# SnowFlake.net
KiCad netlist of a schematic drawn in EAGLE
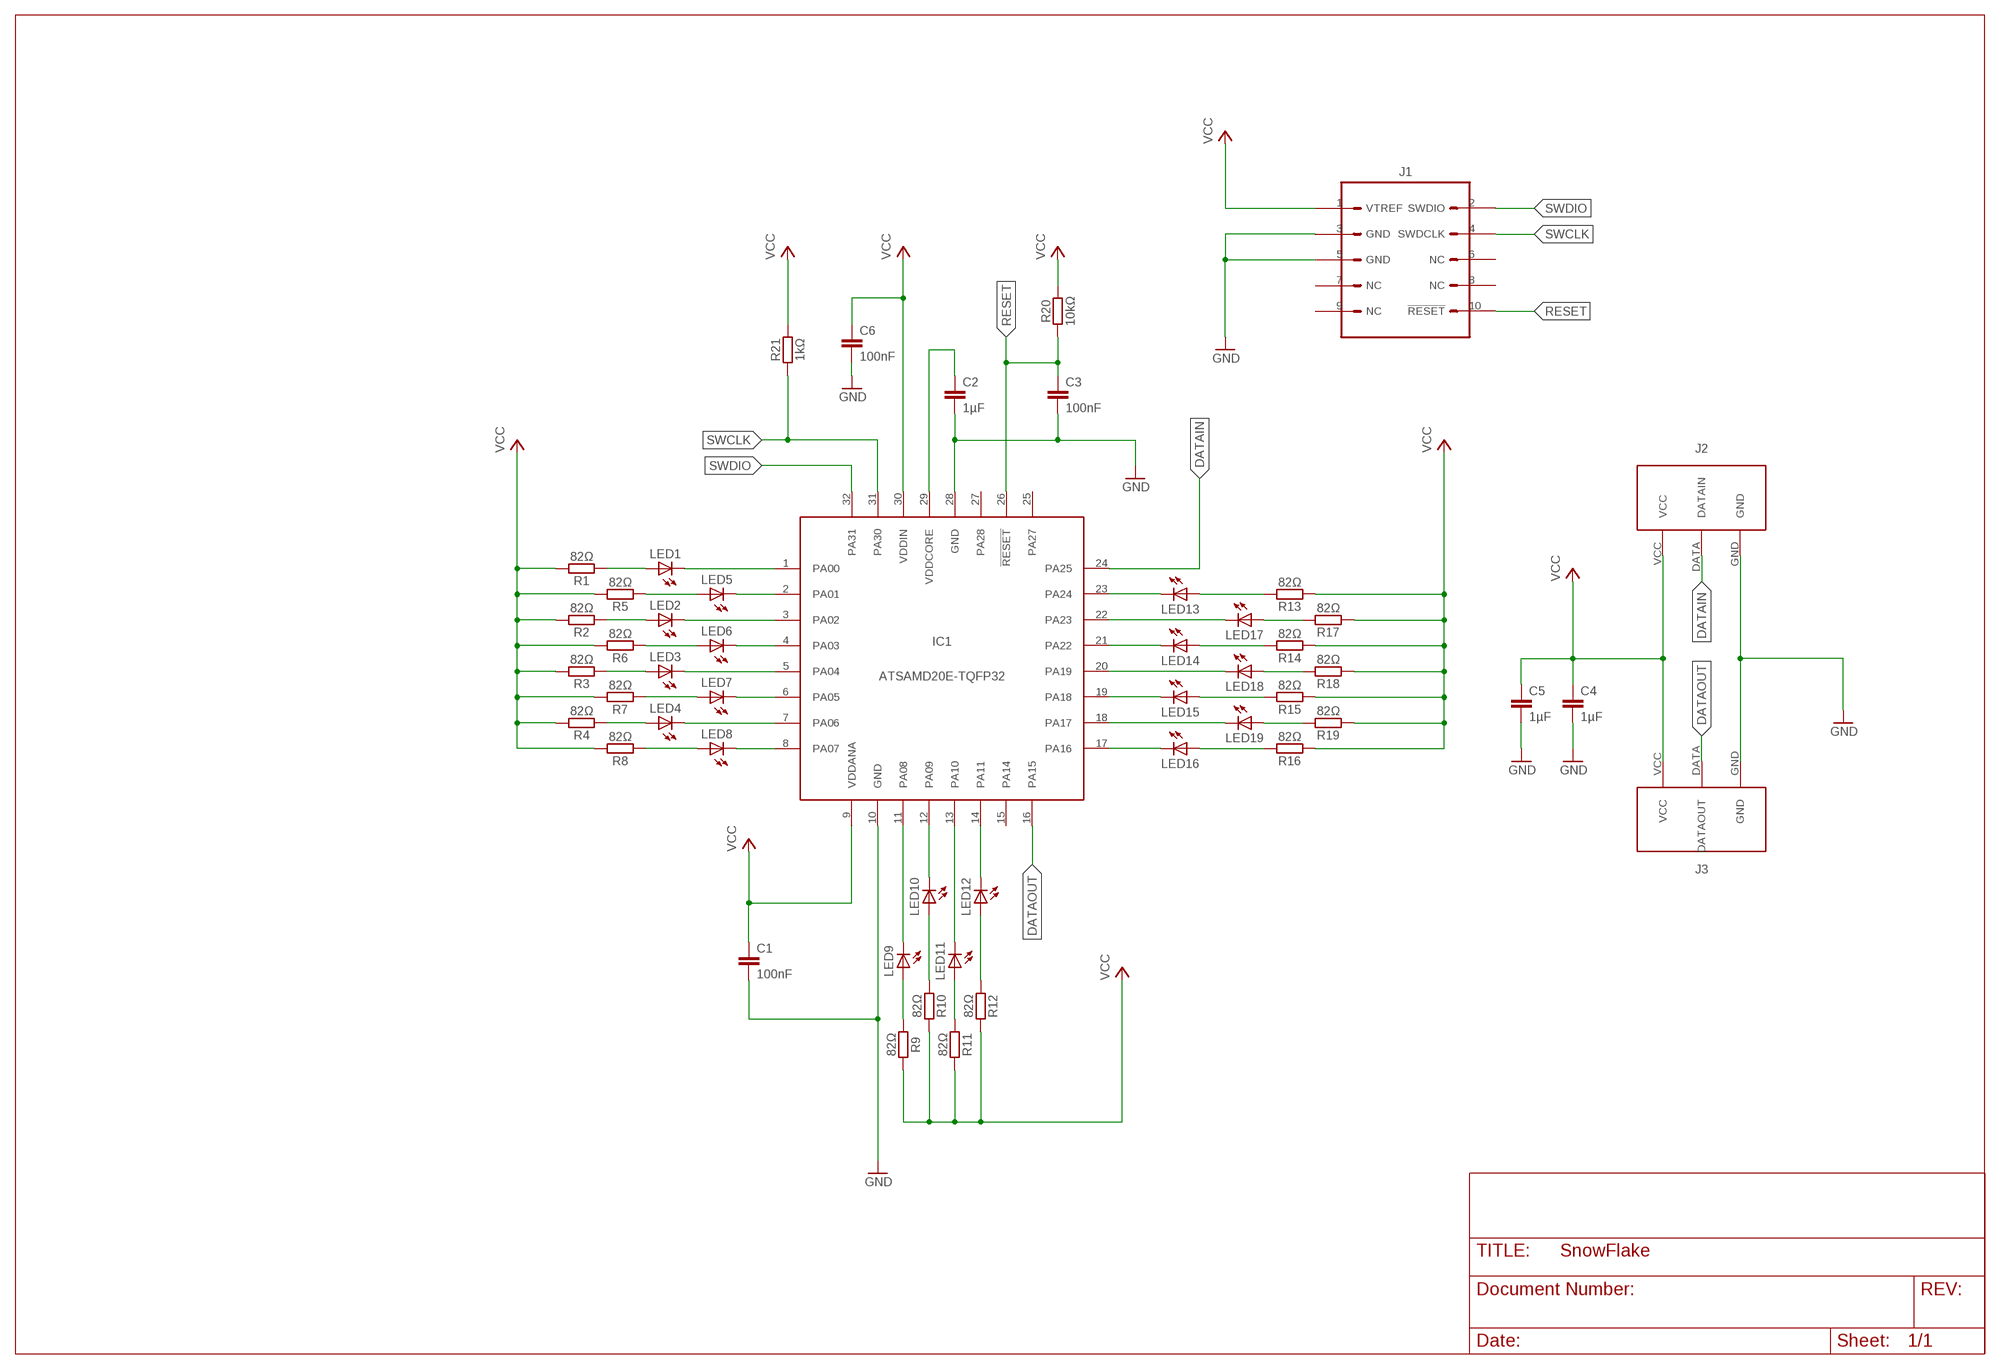
[diagram p0: schematic, sheet 1]

(export (version "E")
  (design (tool "Eeschema 10.0.6"))
  (components
    (comp (ref "C1")
      (value "100nF")
      (footprint "eagle-import:CAPACITOR-0805-MURATA-GRM-21")
      (libsource (lib "eagle-import") (part "C0805-MURATA-GRM-21"))
    )
    (comp (ref "C2")
      (value "1µF")
      (footprint "eagle-import:CAPACITOR-0805-MURATA-GRM-21")
      (libsource (lib "eagle-import") (part "C0805-MURATA-GRM-21"))
    )
    (comp (ref "C3")
      (value "100nF")
      (footprint "eagle-import:CAPACITOR-0805-MURATA-GRM-21")
      (libsource (lib "eagle-import") (part "C0805-MURATA-GRM-21"))
    )
    (comp (ref "C4")
      (value "1µF")
      (footprint "eagle-import:CAPACITOR-0805-MURATA-GRM-21")
      (libsource (lib "eagle-import") (part "C0805-MURATA-GRM-21"))
    )
    (comp (ref "C5")
      (value "1µF")
      (footprint "eagle-import:CAPACITOR-0805-MURATA-GRM-21")
      (libsource (lib "eagle-import") (part "C0805-MURATA-GRM-21"))
    )
    (comp (ref "C6")
      (value "100nF")
      (footprint "eagle-import:CAPACITOR-0805-MURATA-GRM-21")
      (libsource (lib "eagle-import") (part "C0805-MURATA-GRM-21"))
    )
    (comp (ref "IC1")
      (value "ATSAMD20E-TQFP32")
      (footprint "eagle-import:TQFP32-08")
      (libsource (lib "eagle-import") (part "ATSAMD20E-TQFP32"))
    )
    (comp (ref "J1")
      (value "CON-CORTEX-DEBUG-SMD1.27")
      (footprint "eagle-import:CON-2X5-HARWIN-1.27")
      (libsource (lib "eagle-import") (part "CON-CORTEX-DEBUG-SMD1.27"))
    )
    (comp (ref "J2")
      (value "CON-SNOWF-IN")
      (footprint "eagle-import:CON-PADS-3XWIRE-B")
      (libsource (lib "eagle-import") (part "CON-SNOWF-IN"))
    )
    (comp (ref "J3")
      (value "CON-SNOWF-OUT")
      (footprint "eagle-import:CON-PADS-3XWIRE-T")
      (libsource (lib "eagle-import") (part "CON-SNOWF-OUT"))
    )
    (comp (ref "LED1")
      (value "LED0402")
      (footprint "eagle-import:LED-0402-ROHM")
      (libsource (lib "eagle-import") (part "LED0402"))
    )
    (comp (ref "LED2")
      (value "LED0402")
      (footprint "eagle-import:LED-0402-ROHM")
      (libsource (lib "eagle-import") (part "LED0402"))
    )
    (comp (ref "LED3")
      (value "LED0402")
      (footprint "eagle-import:LED-0402-ROHM")
      (libsource (lib "eagle-import") (part "LED0402"))
    )
    (comp (ref "LED4")
      (value "LED0402")
      (footprint "eagle-import:LED-0402-ROHM")
      (libsource (lib "eagle-import") (part "LED0402"))
    )
    (comp (ref "LED5")
      (value "LED0402")
      (footprint "eagle-import:LED-0402-ROHM")
      (libsource (lib "eagle-import") (part "LED0402"))
    )
    (comp (ref "LED6")
      (value "LED0402")
      (footprint "eagle-import:LED-0402-ROHM")
      (libsource (lib "eagle-import") (part "LED0402"))
    )
    (comp (ref "LED7")
      (value "LED0402")
      (footprint "eagle-import:LED-0402-ROHM")
      (libsource (lib "eagle-import") (part "LED0402"))
    )
    (comp (ref "LED8")
      (value "LED0402")
      (footprint "eagle-import:LED-0402-ROHM")
      (libsource (lib "eagle-import") (part "LED0402"))
    )
    (comp (ref "LED9")
      (value "LED0402")
      (footprint "eagle-import:LED-0402-ROHM")
      (libsource (lib "eagle-import") (part "LED0402"))
    )
    (comp (ref "LED10")
      (value "LED0402")
      (footprint "eagle-import:LED-0402-ROHM")
      (libsource (lib "eagle-import") (part "LED0402"))
    )
    (comp (ref "LED11")
      (value "LED0402")
      (footprint "eagle-import:LED-0402-ROHM")
      (libsource (lib "eagle-import") (part "LED0402"))
    )
    (comp (ref "LED12")
      (value "LED0402")
      (footprint "eagle-import:LED-0402-ROHM")
      (libsource (lib "eagle-import") (part "LED0402"))
    )
    (comp (ref "LED13")
      (value "LED0402")
      (footprint "eagle-import:LED-0402-ROHM")
      (libsource (lib "eagle-import") (part "LED0402"))
    )
    (comp (ref "LED14")
      (value "LED0402")
      (footprint "eagle-import:LED-0402-ROHM")
      (libsource (lib "eagle-import") (part "LED0402"))
    )
    (comp (ref "LED15")
      (value "LED0402")
      (footprint "eagle-import:LED-0402-ROHM")
      (libsource (lib "eagle-import") (part "LED0402"))
    )
    (comp (ref "LED16")
      (value "LED0402")
      (footprint "eagle-import:LED-0402-ROHM")
      (libsource (lib "eagle-import") (part "LED0402"))
    )
    (comp (ref "LED17")
      (value "LED0402")
      (footprint "eagle-import:LED-0402-ROHM")
      (libsource (lib "eagle-import") (part "LED0402"))
    )
    (comp (ref "LED18")
      (value "LED0402")
      (footprint "eagle-import:LED-0402-ROHM")
      (libsource (lib "eagle-import") (part "LED0402"))
    )
    (comp (ref "LED19")
      (value "LED0402")
      (footprint "eagle-import:LED-0402-ROHM")
      (libsource (lib "eagle-import") (part "LED0402"))
    )
    (comp (ref "R1")
      (value "82Ω")
      (footprint "eagle-import:RESISTOR-0805-KOA-RK73-2A")
      (libsource (lib "eagle-import") (part "RESISTOR0805-KOA-RK73-2A"))
    )
    (comp (ref "R2")
      (value "82Ω")
      (footprint "eagle-import:RESISTOR-0805-KOA-RK73-2A")
      (libsource (lib "eagle-import") (part "RESISTOR0805-KOA-RK73-2A"))
    )
    (comp (ref "R3")
      (value "82Ω")
      (footprint "eagle-import:RESISTOR-0805-KOA-RK73-2A")
      (libsource (lib "eagle-import") (part "RESISTOR0805-KOA-RK73-2A"))
    )
    (comp (ref "R4")
      (value "82Ω")
      (footprint "eagle-import:RESISTOR-0805-KOA-RK73-2A")
      (libsource (lib "eagle-import") (part "RESISTOR0805-KOA-RK73-2A"))
    )
    (comp (ref "R5")
      (value "82Ω")
      (footprint "eagle-import:RESISTOR-0805-KOA-RK73-2A")
      (libsource (lib "eagle-import") (part "RESISTOR0805-KOA-RK73-2A"))
    )
    (comp (ref "R6")
      (value "82Ω")
      (footprint "eagle-import:RESISTOR-0805-KOA-RK73-2A")
      (libsource (lib "eagle-import") (part "RESISTOR0805-KOA-RK73-2A"))
    )
    (comp (ref "R7")
      (value "82Ω")
      (footprint "eagle-import:RESISTOR-0805-KOA-RK73-2A")
      (libsource (lib "eagle-import") (part "RESISTOR0805-KOA-RK73-2A"))
    )
    (comp (ref "R8")
      (value "82Ω")
      (footprint "eagle-import:RESISTOR-0805-KOA-RK73-2A")
      (libsource (lib "eagle-import") (part "RESISTOR0805-KOA-RK73-2A"))
    )
    (comp (ref "R9")
      (value "82Ω")
      (footprint "eagle-import:RESISTOR-0805-KOA-RK73-2A")
      (libsource (lib "eagle-import") (part "RESISTOR0805-KOA-RK73-2A"))
    )
    (comp (ref "R10")
      (value "82Ω")
      (footprint "eagle-import:RESISTOR-0805-KOA-RK73-2A")
      (libsource (lib "eagle-import") (part "RESISTOR0805-KOA-RK73-2A"))
    )
    (comp (ref "R11")
      (value "82Ω")
      (footprint "eagle-import:RESISTOR-0805-KOA-RK73-2A")
      (libsource (lib "eagle-import") (part "RESISTOR0805-KOA-RK73-2A"))
    )
    (comp (ref "R12")
      (value "82Ω")
      (footprint "eagle-import:RESISTOR-0805-KOA-RK73-2A")
      (libsource (lib "eagle-import") (part "RESISTOR0805-KOA-RK73-2A"))
    )
    (comp (ref "R13")
      (value "82Ω")
      (footprint "eagle-import:RESISTOR-0805-KOA-RK73-2A")
      (libsource (lib "eagle-import") (part "RESISTOR0805-KOA-RK73-2A"))
    )
    (comp (ref "R14")
      (value "82Ω")
      (footprint "eagle-import:RESISTOR-0805-KOA-RK73-2A")
      (libsource (lib "eagle-import") (part "RESISTOR0805-KOA-RK73-2A"))
    )
    (comp (ref "R15")
      (value "82Ω")
      (footprint "eagle-import:RESISTOR-0805-KOA-RK73-2A")
      (libsource (lib "eagle-import") (part "RESISTOR0805-KOA-RK73-2A"))
    )
    (comp (ref "R16")
      (value "82Ω")
      (footprint "eagle-import:RESISTOR-0805-KOA-RK73-2A")
      (libsource (lib "eagle-import") (part "RESISTOR0805-KOA-RK73-2A"))
    )
    (comp (ref "R17")
      (value "82Ω")
      (footprint "eagle-import:RESISTOR-0805-KOA-RK73-2A")
      (libsource (lib "eagle-import") (part "RESISTOR0805-KOA-RK73-2A"))
    )
    (comp (ref "R18")
      (value "82Ω")
      (footprint "eagle-import:RESISTOR-0805-KOA-RK73-2A")
      (libsource (lib "eagle-import") (part "RESISTOR0805-KOA-RK73-2A"))
    )
    (comp (ref "R19")
      (value "82Ω")
      (footprint "eagle-import:RESISTOR-0805-KOA-RK73-2A")
      (libsource (lib "eagle-import") (part "RESISTOR0805-KOA-RK73-2A"))
    )
    (comp (ref "R20")
      (value "10kΩ")
      (footprint "eagle-import:RESISTOR-0805-KOA-RK73-2A")
      (libsource (lib "eagle-import") (part "RESISTOR0805-KOA-RK73-2A"))
    )
    (comp (ref "R21")
      (value "1kΩ")
      (footprint "eagle-import:RESISTOR-0805-KOA-RK73-2A")
      (libsource (lib "eagle-import") (part "RESISTOR0805-KOA-RK73-2A"))
    )
  )
  (nets
    (net (code "1") (name "DATAIN") (class "Default")
      (node (ref "IC1") (pin "24") (pinfunction "PA25_24") (pintype "bidirectional"))
      (node (ref "J2") (pin "DATA") (pinfunction "DATAIN_DATA") (pintype "input"))
    )
    (net (code "2") (name "DATAOUT") (class "Default")
      (node (ref "IC1") (pin "16") (pinfunction "PA15_16") (pintype "bidirectional"))
      (node (ref "J3") (pin "DATA") (pinfunction "DATAOUT_DATA") (pintype "output"))
    )
    (net (code "3") (name "GND") (class "Default")
      (node (ref "C1") (pin "2") (pinfunction "2_2") (pintype "passive"))
      (node (ref "C2") (pin "2") (pinfunction "2_2") (pintype "passive"))
      (node (ref "C3") (pin "2") (pinfunction "2_2") (pintype "passive"))
      (node (ref "C4") (pin "2") (pinfunction "2_2") (pintype "passive"))
      (node (ref "C5") (pin "2") (pinfunction "2_2") (pintype "passive"))
      (node (ref "C6") (pin "2") (pinfunction "2_2") (pintype "passive"))
      (node (ref "IC1") (pin "10") (pinfunction "GND_10") (pintype "bidirectional"))
      (node (ref "IC1") (pin "28") (pinfunction "GND_28") (pintype "bidirectional"))
      (node (ref "J1") (pin "3") (pinfunction "GND_3") (pintype "bidirectional"))
      (node (ref "J1") (pin "5") (pinfunction "GND_5") (pintype "bidirectional"))
      (node (ref "J2") (pin "GND") (pinfunction "GND_GND") (pintype "power_in"))
      (node (ref "J3") (pin "GND") (pinfunction "GND_GND") (pintype "power_in"))
    )
    (net (code "4") (name "Net-(IC1-PA00)") (class "Default")
      (node (ref "IC1") (pin "1") (pinfunction "PA00_1") (pintype "bidirectional"))
      (node (ref "LED1") (pin "C") (pinfunction "C_C") (pintype "passive"))
    )
    (net (code "5") (name "Net-(IC1-PA01)") (class "Default")
      (node (ref "IC1") (pin "2") (pinfunction "PA01_2") (pintype "bidirectional"))
      (node (ref "LED5") (pin "C") (pinfunction "C_C") (pintype "passive"))
    )
    (net (code "6") (name "Net-(IC1-PA02)") (class "Default")
      (node (ref "IC1") (pin "3") (pinfunction "PA02_3") (pintype "bidirectional"))
      (node (ref "LED2") (pin "C") (pinfunction "C_C") (pintype "passive"))
    )
    (net (code "7") (name "Net-(IC1-PA03)") (class "Default")
      (node (ref "IC1") (pin "4") (pinfunction "PA03_4") (pintype "bidirectional"))
      (node (ref "LED6") (pin "C") (pinfunction "C_C") (pintype "passive"))
    )
    (net (code "8") (name "Net-(IC1-PA04)") (class "Default")
      (node (ref "IC1") (pin "5") (pinfunction "PA04_5") (pintype "bidirectional"))
      (node (ref "LED3") (pin "C") (pinfunction "C_C") (pintype "passive"))
    )
    (net (code "9") (name "Net-(IC1-PA05)") (class "Default")
      (node (ref "IC1") (pin "6") (pinfunction "PA05_6") (pintype "bidirectional"))
      (node (ref "LED7") (pin "C") (pinfunction "C_C") (pintype "passive"))
    )
    (net (code "10") (name "Net-(IC1-PA06)") (class "Default")
      (node (ref "IC1") (pin "7") (pinfunction "PA06_7") (pintype "bidirectional"))
      (node (ref "LED4") (pin "C") (pinfunction "C_C") (pintype "passive"))
    )
    (net (code "11") (name "Net-(IC1-PA07)") (class "Default")
      (node (ref "IC1") (pin "8") (pinfunction "PA07_8") (pintype "bidirectional"))
      (node (ref "LED8") (pin "C") (pinfunction "C_C") (pintype "passive"))
    )
    (net (code "12") (name "Net-(IC1-PA08)") (class "Default")
      (node (ref "IC1") (pin "11") (pinfunction "PA08_11") (pintype "bidirectional"))
      (node (ref "LED9") (pin "C") (pinfunction "C_C") (pintype "passive"))
    )
    (net (code "13") (name "Net-(IC1-PA09)") (class "Default")
      (node (ref "IC1") (pin "12") (pinfunction "PA09_12") (pintype "bidirectional"))
      (node (ref "LED10") (pin "C") (pinfunction "C_C") (pintype "passive"))
    )
    (net (code "14") (name "Net-(IC1-PA10)") (class "Default")
      (node (ref "IC1") (pin "13") (pinfunction "PA10_13") (pintype "bidirectional"))
      (node (ref "LED11") (pin "C") (pinfunction "C_C") (pintype "passive"))
    )
    (net (code "15") (name "Net-(IC1-PA11)") (class "Default")
      (node (ref "IC1") (pin "14") (pinfunction "PA11_14") (pintype "bidirectional"))
      (node (ref "LED12") (pin "C") (pinfunction "C_C") (pintype "passive"))
    )
    (net (code "16") (name "Net-(IC1-PA16)") (class "Default")
      (node (ref "IC1") (pin "17") (pinfunction "PA16_17") (pintype "bidirectional"))
      (node (ref "LED16") (pin "C") (pinfunction "C_C") (pintype "passive"))
    )
    (net (code "17") (name "Net-(IC1-PA17)") (class "Default")
      (node (ref "IC1") (pin "18") (pinfunction "PA17_18") (pintype "bidirectional"))
      (node (ref "LED19") (pin "C") (pinfunction "C_C") (pintype "passive"))
    )
    (net (code "18") (name "Net-(IC1-PA18)") (class "Default")
      (node (ref "IC1") (pin "19") (pinfunction "PA18_19") (pintype "bidirectional"))
      (node (ref "LED15") (pin "C") (pinfunction "C_C") (pintype "passive"))
    )
    (net (code "19") (name "Net-(IC1-PA19)") (class "Default")
      (node (ref "IC1") (pin "20") (pinfunction "PA19_20") (pintype "bidirectional"))
      (node (ref "LED18") (pin "C") (pinfunction "C_C") (pintype "passive"))
    )
    (net (code "20") (name "Net-(IC1-PA22)") (class "Default")
      (node (ref "IC1") (pin "21") (pinfunction "PA22_21") (pintype "bidirectional"))
      (node (ref "LED14") (pin "C") (pinfunction "C_C") (pintype "passive"))
    )
    (net (code "21") (name "Net-(IC1-PA23)") (class "Default")
      (node (ref "IC1") (pin "22") (pinfunction "PA23_22") (pintype "bidirectional"))
      (node (ref "LED17") (pin "C") (pinfunction "C_C") (pintype "passive"))
    )
    (net (code "22") (name "Net-(IC1-PA24)") (class "Default")
      (node (ref "IC1") (pin "23") (pinfunction "PA24_23") (pintype "bidirectional"))
      (node (ref "LED13") (pin "C") (pinfunction "C_C") (pintype "passive"))
    )
    (net (code "23") (name "Net-(IC1-VDDCORE)") (class "Default")
      (node (ref "C2") (pin "1") (pinfunction "1_1") (pintype "passive"))
      (node (ref "IC1") (pin "29") (pinfunction "VDDCORE_29") (pintype "bidirectional"))
    )
    (net (code "24") (name "Net-(LED1-PadA)") (class "Default")
      (node (ref "LED1") (pin "A") (pinfunction "A_A") (pintype "passive"))
      (node (ref "R1") (pin "1") (pinfunction "1_1") (pintype "passive"))
    )
    (net (code "25") (name "Net-(LED2-PadA)") (class "Default")
      (node (ref "LED2") (pin "A") (pinfunction "A_A") (pintype "passive"))
      (node (ref "R2") (pin "1") (pinfunction "1_1") (pintype "passive"))
    )
    (net (code "26") (name "Net-(LED3-PadA)") (class "Default")
      (node (ref "LED3") (pin "A") (pinfunction "A_A") (pintype "passive"))
      (node (ref "R3") (pin "1") (pinfunction "1_1") (pintype "passive"))
    )
    (net (code "27") (name "Net-(LED4-PadA)") (class "Default")
      (node (ref "LED4") (pin "A") (pinfunction "A_A") (pintype "passive"))
      (node (ref "R4") (pin "1") (pinfunction "1_1") (pintype "passive"))
    )
    (net (code "28") (name "Net-(LED5-PadA)") (class "Default")
      (node (ref "LED5") (pin "A") (pinfunction "A_A") (pintype "passive"))
      (node (ref "R5") (pin "1") (pinfunction "1_1") (pintype "passive"))
    )
    (net (code "29") (name "Net-(LED6-PadA)") (class "Default")
      (node (ref "LED6") (pin "A") (pinfunction "A_A") (pintype "passive"))
      (node (ref "R6") (pin "1") (pinfunction "1_1") (pintype "passive"))
    )
    (net (code "30") (name "Net-(LED7-PadA)") (class "Default")
      (node (ref "LED7") (pin "A") (pinfunction "A_A") (pintype "passive"))
      (node (ref "R7") (pin "1") (pinfunction "1_1") (pintype "passive"))
    )
    (net (code "31") (name "Net-(LED8-PadA)") (class "Default")
      (node (ref "LED8") (pin "A") (pinfunction "A_A") (pintype "passive"))
      (node (ref "R8") (pin "1") (pinfunction "1_1") (pintype "passive"))
    )
    (net (code "32") (name "Net-(LED9-PadA)") (class "Default")
      (node (ref "LED9") (pin "A") (pinfunction "A_A") (pintype "passive"))
      (node (ref "R9") (pin "1") (pinfunction "1_1") (pintype "passive"))
    )
    (net (code "33") (name "Net-(LED10-PadA)") (class "Default")
      (node (ref "LED10") (pin "A") (pinfunction "A_A") (pintype "passive"))
      (node (ref "R10") (pin "1") (pinfunction "1_1") (pintype "passive"))
    )
    (net (code "34") (name "Net-(LED11-PadA)") (class "Default")
      (node (ref "LED11") (pin "A") (pinfunction "A_A") (pintype "passive"))
      (node (ref "R11") (pin "1") (pinfunction "1_1") (pintype "passive"))
    )
    (net (code "35") (name "Net-(LED12-PadA)") (class "Default")
      (node (ref "LED12") (pin "A") (pinfunction "A_A") (pintype "passive"))
      (node (ref "R12") (pin "1") (pinfunction "1_1") (pintype "passive"))
    )
    (net (code "36") (name "Net-(LED13-PadA)") (class "Default")
      (node (ref "LED13") (pin "A") (pinfunction "A_A") (pintype "passive"))
      (node (ref "R13") (pin "2") (pinfunction "2_2") (pintype "passive"))
    )
    (net (code "37") (name "Net-(LED14-PadA)") (class "Default")
      (node (ref "LED14") (pin "A") (pinfunction "A_A") (pintype "passive"))
      (node (ref "R14") (pin "2") (pinfunction "2_2") (pintype "passive"))
    )
    (net (code "38") (name "Net-(LED15-PadA)") (class "Default")
      (node (ref "LED15") (pin "A") (pinfunction "A_A") (pintype "passive"))
      (node (ref "R15") (pin "2") (pinfunction "2_2") (pintype "passive"))
    )
    (net (code "39") (name "Net-(LED16-PadA)") (class "Default")
      (node (ref "LED16") (pin "A") (pinfunction "A_A") (pintype "passive"))
      (node (ref "R16") (pin "2") (pinfunction "2_2") (pintype "passive"))
    )
    (net (code "40") (name "Net-(LED17-PadA)") (class "Default")
      (node (ref "LED17") (pin "A") (pinfunction "A_A") (pintype "passive"))
      (node (ref "R17") (pin "2") (pinfunction "2_2") (pintype "passive"))
    )
    (net (code "41") (name "Net-(LED18-PadA)") (class "Default")
      (node (ref "LED18") (pin "A") (pinfunction "A_A") (pintype "passive"))
      (node (ref "R18") (pin "2") (pinfunction "2_2") (pintype "passive"))
    )
    (net (code "42") (name "Net-(LED19-PadA)") (class "Default")
      (node (ref "LED19") (pin "A") (pinfunction "A_A") (pintype "passive"))
      (node (ref "R19") (pin "2") (pinfunction "2_2") (pintype "passive"))
    )
    (net (code "43") (name "RESET") (class "Default")
      (node (ref "C3") (pin "1") (pinfunction "1_1") (pintype "passive"))
      (node (ref "IC1") (pin "26") (pinfunction "~{RESET}_26") (pintype "bidirectional"))
      (node (ref "J1") (pin "10") (pinfunction "~{RESET}_10") (pintype "power_in"))
      (node (ref "R20") (pin "1") (pinfunction "1_1") (pintype "passive"))
    )
    (net (code "44") (name "SWCLK") (class "Default")
      (node (ref "IC1") (pin "31") (pinfunction "PA30_31") (pintype "bidirectional"))
      (node (ref "J1") (pin "4") (pinfunction "SWDCLK_4") (pintype "power_in"))
      (node (ref "R21") (pin "1") (pinfunction "1_1") (pintype "passive"))
    )
    (net (code "45") (name "SWDIO") (class "Default")
      (node (ref "IC1") (pin "32") (pinfunction "PA31_32") (pintype "bidirectional"))
      (node (ref "J1") (pin "2") (pinfunction "SWDIO_2") (pintype "power_in"))
    )
    (net (code "46") (name "VCC") (class "Default")
      (node (ref "C1") (pin "1") (pinfunction "1_1") (pintype "passive"))
      (node (ref "C4") (pin "1") (pinfunction "1_1") (pintype "passive"))
      (node (ref "C5") (pin "1") (pinfunction "1_1") (pintype "passive"))
      (node (ref "C6") (pin "1") (pinfunction "1_1") (pintype "passive"))
      (node (ref "IC1") (pin "30") (pinfunction "VDDIN_30") (pintype "bidirectional"))
      (node (ref "IC1") (pin "9") (pinfunction "VDDANA_9") (pintype "bidirectional"))
      (node (ref "J1") (pin "1") (pinfunction "VTREF_1") (pintype "bidirectional"))
      (node (ref "J2") (pin "VCC") (pinfunction "VCC_VCC") (pintype "power_in"))
      (node (ref "J3") (pin "VCC") (pinfunction "VCC_VCC") (pintype "power_in"))
      (node (ref "R1") (pin "2") (pinfunction "2_2") (pintype "passive"))
      (node (ref "R10") (pin "2") (pinfunction "2_2") (pintype "passive"))
      (node (ref "R11") (pin "2") (pinfunction "2_2") (pintype "passive"))
      (node (ref "R12") (pin "2") (pinfunction "2_2") (pintype "passive"))
      (node (ref "R13") (pin "1") (pinfunction "1_1") (pintype "passive"))
      (node (ref "R14") (pin "1") (pinfunction "1_1") (pintype "passive"))
      (node (ref "R15") (pin "1") (pinfunction "1_1") (pintype "passive"))
      (node (ref "R16") (pin "1") (pinfunction "1_1") (pintype "passive"))
      (node (ref "R17") (pin "1") (pinfunction "1_1") (pintype "passive"))
      (node (ref "R18") (pin "1") (pinfunction "1_1") (pintype "passive"))
      (node (ref "R19") (pin "1") (pinfunction "1_1") (pintype "passive"))
      (node (ref "R2") (pin "2") (pinfunction "2_2") (pintype "passive"))
      (node (ref "R20") (pin "2") (pinfunction "2_2") (pintype "passive"))
      (node (ref "R21") (pin "2") (pinfunction "2_2") (pintype "passive"))
      (node (ref "R3") (pin "2") (pinfunction "2_2") (pintype "passive"))
      (node (ref "R4") (pin "2") (pinfunction "2_2") (pintype "passive"))
      (node (ref "R5") (pin "2") (pinfunction "2_2") (pintype "passive"))
      (node (ref "R6") (pin "2") (pinfunction "2_2") (pintype "passive"))
      (node (ref "R7") (pin "2") (pinfunction "2_2") (pintype "passive"))
      (node (ref "R8") (pin "2") (pinfunction "2_2") (pintype "passive"))
      (node (ref "R9") (pin "2") (pinfunction "2_2") (pintype "passive"))
    )
    (net (code "47") (name "unconnected-(IC1-PA14-Pad15)") (class "Default")
      (node (ref "IC1") (pin "15") (pinfunction "PA14_15") (pintype "bidirectional"))
    )
    (net (code "48") (name "unconnected-(IC1-PA27-Pad25)") (class "Default")
      (node (ref "IC1") (pin "25") (pinfunction "PA27_25") (pintype "bidirectional"))
    )
    (net (code "49") (name "unconnected-(IC1-PA28-Pad27)") (class "Default")
      (node (ref "IC1") (pin "27") (pinfunction "PA28_27") (pintype "bidirectional"))
    )
    (net (code "50") (name "unconnected-(J1-NC-Pad6)") (class "Default")
      (node (ref "J1") (pin "6") (pinfunction "NC_6") (pintype "bidirectional"))
    )
    (net (code "51") (name "unconnected-(J1-NC-Pad7)") (class "Default")
      (node (ref "J1") (pin "7") (pinfunction "NC_7") (pintype "no_connect"))
    )
    (net (code "52") (name "unconnected-(J1-NC-Pad8)") (class "Default")
      (node (ref "J1") (pin "8") (pinfunction "NC_8") (pintype "bidirectional"))
    )
    (net (code "53") (name "unconnected-(J1-NC-Pad9)") (class "Default")
      (node (ref "J1") (pin "9") (pinfunction "NC_9") (pintype "bidirectional"))
    )
  )
)
